# Simon.net
KiCad netlist of a schematic drawn in EAGLE
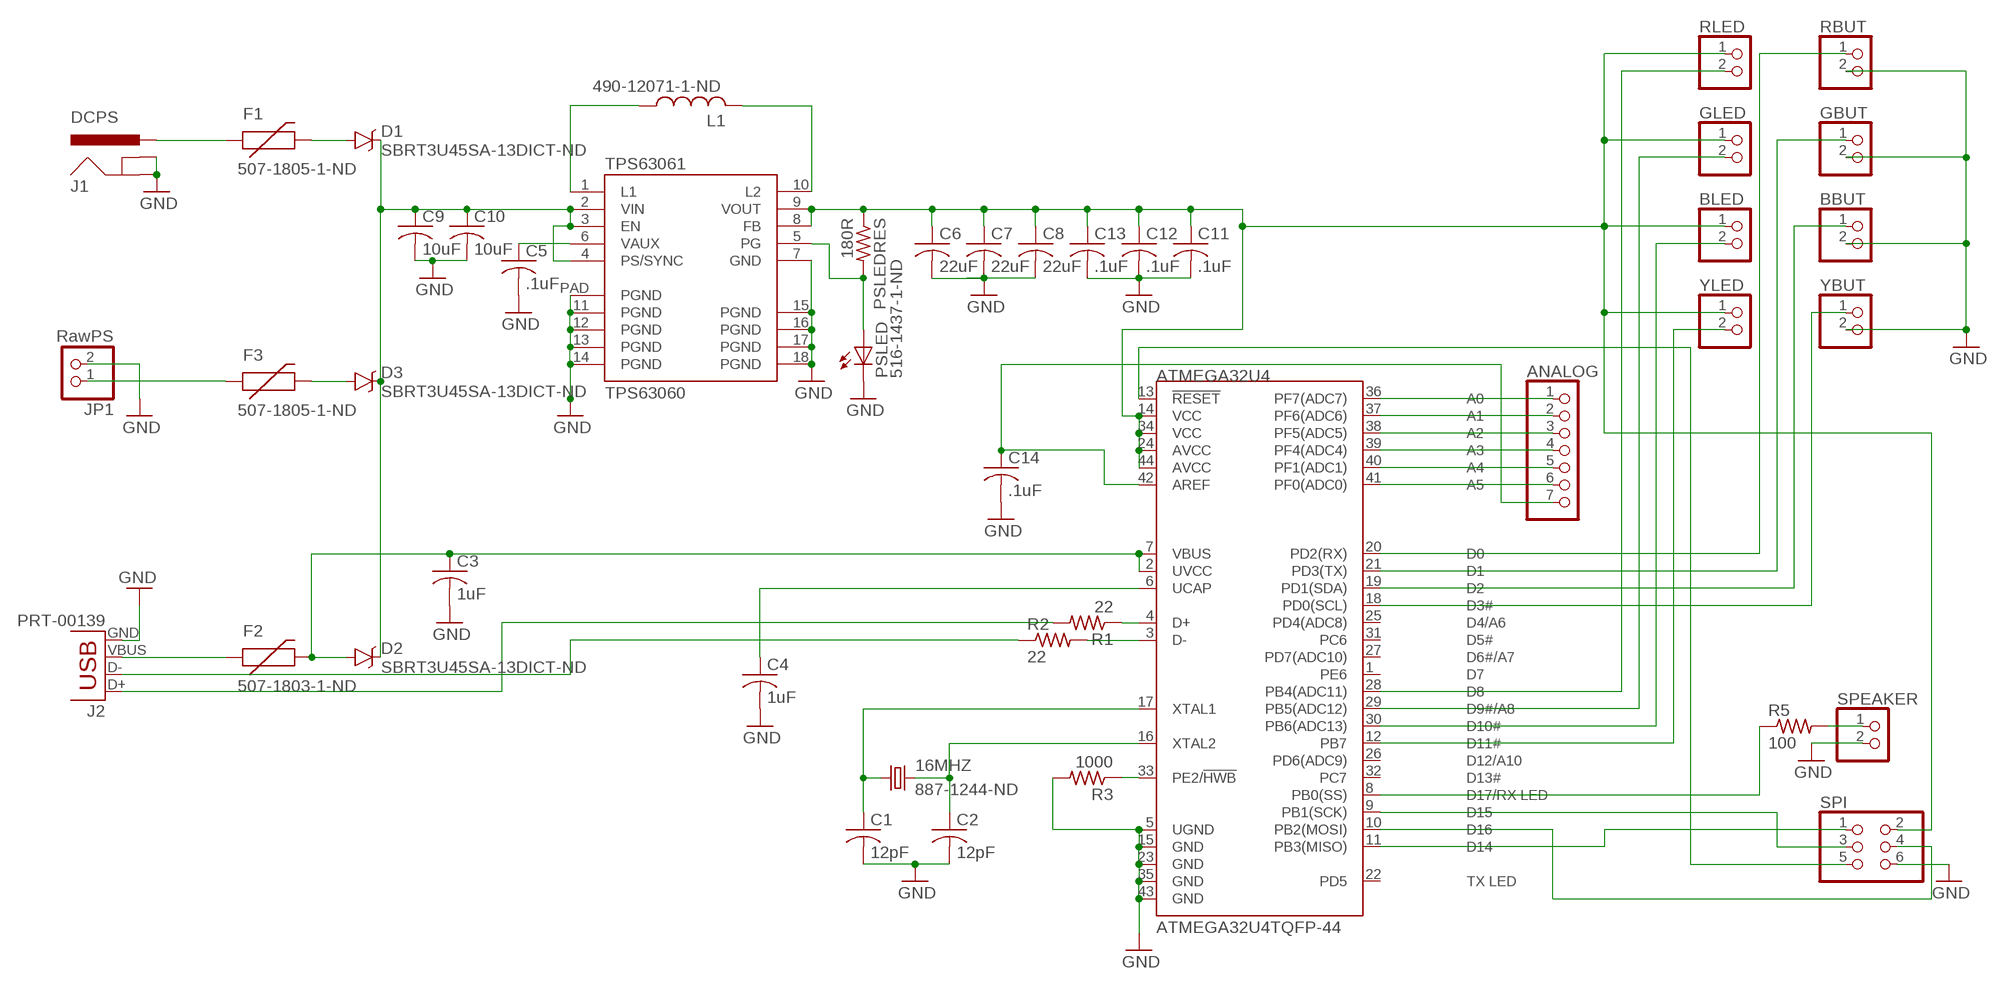
[diagram p0: schematic, sheet 1]

(export (version "E")
  (design (tool "Eeschema 10.0.6"))
  (components
    (comp (ref "16MHZ")
      (value "887-1244-ND")
      (footprint "eagle-import:HC49US")
      (libsource (lib "eagle-import") (part "CRYSTALHC49US"))
    )
    (comp (ref "ANALOG")
      (value "PINHD-1X7")
      (footprint "eagle-import:1X07")
      (libsource (lib "eagle-import") (part "PINHD-1X7"))
    )
    (comp (ref "ATMEGA32U4")
      (value "ATMEGA32U4TQFP-44")
      (footprint "eagle-import:TQFP44")
      (libsource (lib "eagle-import") (part "ATMEGA32U4TQFP-44"))
    )
    (comp (ref "BBUT")
      (value "PINHD-1X2")
      (footprint "eagle-import:1X02")
      (libsource (lib "eagle-import") (part "PINHD-1X2"))
    )
    (comp (ref "BLED")
      (value "PINHD-1X2")
      (footprint "eagle-import:1X02")
      (libsource (lib "eagle-import") (part "PINHD-1X2"))
    )
    (comp (ref "C1")
      (value "12pF")
      (footprint "eagle-import:C0805")
      (libsource (lib "eagle-import") (part "C-USC0805"))
    )
    (comp (ref "C2")
      (value "12pF")
      (footprint "eagle-import:C0805")
      (libsource (lib "eagle-import") (part "C-USC0805"))
    )
    (comp (ref "C3")
      (value "1uF")
      (footprint "eagle-import:C0805")
      (libsource (lib "eagle-import") (part "C-USC0805"))
    )
    (comp (ref "C4")
      (value "1uF")
      (footprint "eagle-import:C0805")
      (libsource (lib "eagle-import") (part "C-USC0805"))
    )
    (comp (ref "C5")
      (value ".1uF")
      (footprint "eagle-import:C0805")
      (libsource (lib "eagle-import") (part "C-USC0805"))
    )
    (comp (ref "C6")
      (value "22uF")
      (footprint "eagle-import:C0805")
      (libsource (lib "eagle-import") (part "resistor_C-USC0805"))
    )
    (comp (ref "C7")
      (value "22uF")
      (footprint "eagle-import:C0805")
      (libsource (lib "eagle-import") (part "resistor_C-USC0805"))
    )
    (comp (ref "C8")
      (value "22uF")
      (footprint "eagle-import:C0805")
      (libsource (lib "eagle-import") (part "resistor_C-USC0805"))
    )
    (comp (ref "C9")
      (value "10uF")
      (footprint "eagle-import:C0805")
      (libsource (lib "eagle-import") (part "resistor_C-USC0805"))
    )
    (comp (ref "C10")
      (value "10uF")
      (footprint "eagle-import:C0805")
      (libsource (lib "eagle-import") (part "resistor_C-USC0805"))
    )
    (comp (ref "C11")
      (value ".1uF")
      (footprint "eagle-import:C0805")
      (libsource (lib "eagle-import") (part "C-USC0805"))
    )
    (comp (ref "C12")
      (value ".1uF")
      (footprint "eagle-import:C0805")
      (libsource (lib "eagle-import") (part "C-USC0805"))
    )
    (comp (ref "C13")
      (value ".1uF")
      (footprint "eagle-import:C0805")
      (libsource (lib "eagle-import") (part "C-USC0805"))
    )
    (comp (ref "C14")
      (value ".1uF")
      (footprint "eagle-import:C0805")
      (libsource (lib "eagle-import") (part "C-USC0805"))
    )
    (comp (ref "D1")
      (value "SBRT3U45SA-13DICT-ND")
      (footprint "eagle-import:SMA-DIODE")
      (libsource (lib "eagle-import") (part "MBRA140"))
    )
    (comp (ref "D2")
      (value "SBRT3U45SA-13DICT-ND")
      (footprint "eagle-import:SMA-DIODE")
      (libsource (lib "eagle-import") (part "MBRA140"))
    )
    (comp (ref "D3")
      (value "SBRT3U45SA-13DICT-ND")
      (footprint "eagle-import:SMA-DIODE")
      (libsource (lib "eagle-import") (part "MBRA140"))
    )
    (comp (ref "F1")
      (value "507-1805-1-ND")
      (footprint "eagle-import:PTC-1206-WIDE")
      (libsource (lib "eagle-import") (part "PTCSMD-W"))
    )
    (comp (ref "F2")
      (value "507-1803-1-ND")
      (footprint "eagle-import:PTC-1206-WIDE")
      (libsource (lib "eagle-import") (part "PTCSMD-W"))
    )
    (comp (ref "F3")
      (value "507-1805-1-ND")
      (footprint "eagle-import:PTC-1206-WIDE")
      (libsource (lib "eagle-import") (part "PTCSMD-W"))
    )
    (comp (ref "GBUT")
      (value "PINHD-1X2")
      (footprint "eagle-import:1X02")
      (libsource (lib "eagle-import") (part "PINHD-1X2"))
    )
    (comp (ref "GLED")
      (value "PINHD-1X2")
      (footprint "eagle-import:1X02")
      (libsource (lib "eagle-import") (part "PINHD-1X2"))
    )
    (comp (ref "J1")
      (value "DCPS")
      (footprint "eagle-import:POWER_JACK_SMD")
      (libsource (lib "eagle-import") (part "POWER_JACKSMD"))
    )
    (comp (ref "J2")
      (value "PRT-00139")
      (footprint "eagle-import:USB-B-PTH")
      (libsource (lib "eagle-import") (part "USBPTH"))
    )
    (comp (ref "JP1")
      (value "RawPS")
      (footprint "eagle-import:1X02_90")
      (libsource (lib "eagle-import") (part "PINHD-1X2/90"))
    )
    (comp (ref "L1")
      (value "490-12071-1-ND")
      (footprint "eagle-import:L2012C")
      (libsource (lib "eagle-import") (part "L-USL2012C"))
    )
    (comp (ref "PSLED")
      (value "516-1437-1-ND")
      (footprint "eagle-import:SML0805")
      (libsource (lib "eagle-import") (part "LEDSML0805"))
    )
    (comp (ref "PSLEDRES")
      (value "180R")
      (footprint "eagle-import:R0805")
      (libsource (lib "eagle-import") (part "R-US_R0805"))
    )
    (comp (ref "R1")
      (value "22")
      (footprint "eagle-import:R0805")
      (libsource (lib "eagle-import") (part "R-US_R0805"))
    )
    (comp (ref "R2")
      (value "22")
      (footprint "eagle-import:R0805")
      (libsource (lib "eagle-import") (part "R-US_R0805"))
    )
    (comp (ref "R3")
      (value "1000")
      (footprint "eagle-import:R0805")
      (libsource (lib "eagle-import") (part "R-US_R0805"))
    )
    (comp (ref "R5")
      (value "100")
      (footprint "eagle-import:R0805")
      (libsource (lib "eagle-import") (part "R-US_R0805"))
    )
    (comp (ref "RBUT")
      (value "PINHD-1X2")
      (footprint "eagle-import:1X02")
      (libsource (lib "eagle-import") (part "PINHD-1X2"))
    )
    (comp (ref "RLED")
      (value "PINHD-1X2")
      (footprint "eagle-import:1X02")
      (libsource (lib "eagle-import") (part "PINHD-1X2"))
    )
    (comp (ref "SPEAKER")
      (value "PINHD-1X2")
      (footprint "eagle-import:1X02")
      (libsource (lib "eagle-import") (part "PINHD-1X2"))
    )
    (comp (ref "SPI")
      (value "PINHD-2X3")
      (footprint "eagle-import:2X03")
      (libsource (lib "eagle-import") (part "PINHD-2X3"))
    )
    (comp (ref "TPS63061")
      (value "TPS63060")
      (footprint "eagle-import:QFN-10_PAD-8")
      (libsource (lib "eagle-import") (part "TPS63060"))
    )
    (comp (ref "YBUT")
      (value "PINHD-1X2")
      (footprint "eagle-import:1X02")
      (libsource (lib "eagle-import") (part "PINHD-1X2"))
    )
    (comp (ref "YLED")
      (value "PINHD-1X2")
      (footprint "eagle-import:1X02")
      (libsource (lib "eagle-import") (part "PINHD-1X2"))
    )
  )
  (nets
    (net (code "1") (name "GND") (class "Default")
      (node (ref "ATMEGA32U4") (pin "15") (pinfunction "GND_15") (pintype "bidirectional"))
      (node (ref "ATMEGA32U4") (pin "23") (pinfunction "GND_23") (pintype "bidirectional"))
      (node (ref "ATMEGA32U4") (pin "35") (pinfunction "GND_35") (pintype "bidirectional"))
      (node (ref "ATMEGA32U4") (pin "43") (pinfunction "GND_43") (pintype "bidirectional"))
      (node (ref "ATMEGA32U4") (pin "5") (pinfunction "UGND_5") (pintype "bidirectional"))
      (node (ref "BBUT") (pin "2") (pinfunction "2_2") (pintype "passive"))
      (node (ref "C1") (pin "2") (pinfunction "2_2") (pintype "passive"))
      (node (ref "C10") (pin "2") (pinfunction "2_2") (pintype "passive"))
      (node (ref "C11") (pin "2") (pinfunction "2_2") (pintype "passive"))
      (node (ref "C12") (pin "2") (pinfunction "2_2") (pintype "passive"))
      (node (ref "C13") (pin "2") (pinfunction "2_2") (pintype "passive"))
      (node (ref "C14") (pin "2") (pinfunction "2_2") (pintype "passive"))
      (node (ref "C2") (pin "2") (pinfunction "2_2") (pintype "passive"))
      (node (ref "C3") (pin "2") (pinfunction "2_2") (pintype "passive"))
      (node (ref "C4") (pin "2") (pinfunction "2_2") (pintype "passive"))
      (node (ref "C5") (pin "2") (pinfunction "2_2") (pintype "passive"))
      (node (ref "C6") (pin "2") (pinfunction "2_2") (pintype "passive"))
      (node (ref "C7") (pin "2") (pinfunction "2_2") (pintype "passive"))
      (node (ref "C8") (pin "2") (pinfunction "2_2") (pintype "passive"))
      (node (ref "C9") (pin "2") (pinfunction "2_2") (pintype "passive"))
      (node (ref "GBUT") (pin "2") (pinfunction "2_2") (pintype "passive"))
      (node (ref "J1") (pin "GND") (pinfunction "GNDBREAK_GND") (pintype "bidirectional"))
      (node (ref "J1") (pin "P$4") (pinfunction "GND_P$4") (pintype "bidirectional"))
      (node (ref "J2") (pin "GND") (pinfunction "GND_GND") (pintype "bidirectional"))
      (node (ref "JP1") (pin "2") (pinfunction "2_2") (pintype "passive"))
      (node (ref "PSLED") (pin "C") (pinfunction "C_C") (pintype "passive"))
      (node (ref "R3") (pin "2") (pinfunction "2_2") (pintype "passive"))
      (node (ref "RBUT") (pin "2") (pinfunction "2_2") (pintype "passive"))
      (node (ref "SPEAKER") (pin "2") (pinfunction "2_2") (pintype "passive"))
      (node (ref "SPI") (pin "6") (pinfunction "6_6") (pintype "passive"))
      (node (ref "TPS63061") (pin "11") (pinfunction "PGND_11") (pintype "bidirectional"))
      (node (ref "TPS63061") (pin "12") (pinfunction "PGND_12") (pintype "bidirectional"))
      (node (ref "TPS63061") (pin "13") (pinfunction "PGND_13") (pintype "bidirectional"))
      (node (ref "TPS63061") (pin "14") (pinfunction "PGND_14") (pintype "bidirectional"))
      (node (ref "TPS63061") (pin "15") (pinfunction "PGND_15") (pintype "bidirectional"))
      (node (ref "TPS63061") (pin "16") (pinfunction "PGND_16") (pintype "bidirectional"))
      (node (ref "TPS63061") (pin "17") (pinfunction "PGND_17") (pintype "bidirectional"))
      (node (ref "TPS63061") (pin "18") (pinfunction "PGND_18") (pintype "bidirectional"))
      (node (ref "TPS63061") (pin "7") (pinfunction "GND_7") (pintype "bidirectional"))
      (node (ref "TPS63061") (pin "PAD") (pinfunction "PGND_PAD") (pintype "bidirectional"))
      (node (ref "YBUT") (pin "2") (pinfunction "2_2") (pintype "passive"))
    )
    (net (code "2") (name "Net-(ATMEGA32U4-AREF)") (class "Default")
      (node (ref "ANALOG") (pin "7") (pinfunction "7_7") (pintype "passive"))
      (node (ref "ATMEGA32U4") (pin "42") (pinfunction "AREF_42") (pintype "bidirectional"))
      (node (ref "C14") (pin "1") (pinfunction "1_1") (pintype "passive"))
    )
    (net (code "3") (name "Net-(ATMEGA32U4-D+)") (class "Default")
      (node (ref "ATMEGA32U4") (pin "4") (pinfunction "D+_4") (pintype "bidirectional"))
      (node (ref "R1") (pin "1") (pinfunction "1_1") (pintype "passive"))
    )
    (net (code "4") (name "Net-(ATMEGA32U4-D-)") (class "Default")
      (node (ref "ATMEGA32U4") (pin "3") (pinfunction "D-_3") (pintype "bidirectional"))
      (node (ref "R2") (pin "2") (pinfunction "2_2") (pintype "passive"))
    )
    (net (code "5") (name "Net-(ATMEGA32U4-PB0(SS))") (class "Default")
      (node (ref "ATMEGA32U4") (pin "8") (pinfunction "PB0(SS)_8") (pintype "bidirectional"))
      (node (ref "R5") (pin "1") (pinfunction "1_1") (pintype "passive"))
    )
    (net (code "6") (name "Net-(ATMEGA32U4-PB1(SCK))") (class "Default")
      (node (ref "ATMEGA32U4") (pin "9") (pinfunction "PB1(SCK)_9") (pintype "bidirectional"))
      (node (ref "SPI") (pin "3") (pinfunction "3_3") (pintype "passive"))
    )
    (net (code "7") (name "Net-(ATMEGA32U4-PB2(MOSI))") (class "Default")
      (node (ref "ATMEGA32U4") (pin "10") (pinfunction "PB2(MOSI)_10") (pintype "bidirectional"))
      (node (ref "SPI") (pin "4") (pinfunction "4_4") (pintype "passive"))
    )
    (net (code "8") (name "Net-(ATMEGA32U4-PB3(MISO))") (class "Default")
      (node (ref "ATMEGA32U4") (pin "11") (pinfunction "PB3(MISO)_11") (pintype "bidirectional"))
      (node (ref "SPI") (pin "1") (pinfunction "1_1") (pintype "passive"))
    )
    (net (code "9") (name "Net-(ATMEGA32U4-PB4(ADC11))") (class "Default")
      (node (ref "ATMEGA32U4") (pin "28") (pinfunction "PB4(ADC11)_28") (pintype "bidirectional"))
      (node (ref "RLED") (pin "2") (pinfunction "2_2") (pintype "passive"))
    )
    (net (code "10") (name "Net-(ATMEGA32U4-PB5(ADC12))") (class "Default")
      (node (ref "ATMEGA32U4") (pin "29") (pinfunction "PB5(ADC12)_29") (pintype "bidirectional"))
      (node (ref "GLED") (pin "2") (pinfunction "2_2") (pintype "passive"))
    )
    (net (code "11") (name "Net-(ATMEGA32U4-PB6(ADC13))") (class "Default")
      (node (ref "ATMEGA32U4") (pin "30") (pinfunction "PB6(ADC13)_30") (pintype "bidirectional"))
      (node (ref "BLED") (pin "2") (pinfunction "2_2") (pintype "passive"))
    )
    (net (code "12") (name "Net-(ATMEGA32U4-PB7)") (class "Default")
      (node (ref "ATMEGA32U4") (pin "12") (pinfunction "PB7_12") (pintype "bidirectional"))
      (node (ref "YLED") (pin "2") (pinfunction "2_2") (pintype "passive"))
    )
    (net (code "13") (name "Net-(ATMEGA32U4-PD0(SCL))") (class "Default")
      (node (ref "ATMEGA32U4") (pin "18") (pinfunction "PD0(SCL)_18") (pintype "bidirectional"))
      (node (ref "YBUT") (pin "1") (pinfunction "1_1") (pintype "passive"))
    )
    (net (code "14") (name "Net-(ATMEGA32U4-PD1(SDA))") (class "Default")
      (node (ref "ATMEGA32U4") (pin "19") (pinfunction "PD1(SDA)_19") (pintype "bidirectional"))
      (node (ref "BBUT") (pin "1") (pinfunction "1_1") (pintype "passive"))
    )
    (net (code "15") (name "Net-(ATMEGA32U4-PD2(RX))") (class "Default")
      (node (ref "ATMEGA32U4") (pin "20") (pinfunction "PD2(RX)_20") (pintype "bidirectional"))
      (node (ref "RBUT") (pin "1") (pinfunction "1_1") (pintype "passive"))
    )
    (net (code "16") (name "Net-(ATMEGA32U4-PD3(TX))") (class "Default")
      (node (ref "ATMEGA32U4") (pin "21") (pinfunction "PD3(TX)_21") (pintype "bidirectional"))
      (node (ref "GBUT") (pin "1") (pinfunction "1_1") (pintype "passive"))
    )
    (net (code "17") (name "Net-(ATMEGA32U4-PE2{slash}~{HWB})") (class "Default")
      (node (ref "ATMEGA32U4") (pin "33") (pinfunction "PE2/~{HWB}_33") (pintype "bidirectional"))
      (node (ref "R3") (pin "1") (pinfunction "1_1") (pintype "passive"))
    )
    (net (code "18") (name "Net-(ATMEGA32U4-PF0(ADC0))") (class "Default")
      (node (ref "ANALOG") (pin "6") (pinfunction "6_6") (pintype "passive"))
      (node (ref "ATMEGA32U4") (pin "41") (pinfunction "PF0(ADC0)_41") (pintype "bidirectional"))
    )
    (net (code "19") (name "Net-(ATMEGA32U4-PF1(ADC1))") (class "Default")
      (node (ref "ANALOG") (pin "5") (pinfunction "5_5") (pintype "passive"))
      (node (ref "ATMEGA32U4") (pin "40") (pinfunction "PF1(ADC1)_40") (pintype "bidirectional"))
    )
    (net (code "20") (name "Net-(ATMEGA32U4-PF4(ADC4))") (class "Default")
      (node (ref "ANALOG") (pin "4") (pinfunction "4_4") (pintype "passive"))
      (node (ref "ATMEGA32U4") (pin "39") (pinfunction "PF4(ADC4)_39") (pintype "bidirectional"))
    )
    (net (code "21") (name "Net-(ATMEGA32U4-PF5(ADC5))") (class "Default")
      (node (ref "ANALOG") (pin "3") (pinfunction "3_3") (pintype "passive"))
      (node (ref "ATMEGA32U4") (pin "38") (pinfunction "PF5(ADC5)_38") (pintype "bidirectional"))
    )
    (net (code "22") (name "Net-(ATMEGA32U4-PF6(ADC6))") (class "Default")
      (node (ref "ANALOG") (pin "2") (pinfunction "2_2") (pintype "passive"))
      (node (ref "ATMEGA32U4") (pin "37") (pinfunction "PF6(ADC6)_37") (pintype "bidirectional"))
    )
    (net (code "23") (name "Net-(ATMEGA32U4-PF7(ADC7))") (class "Default")
      (node (ref "ANALOG") (pin "1") (pinfunction "1_1") (pintype "passive"))
      (node (ref "ATMEGA32U4") (pin "36") (pinfunction "PF7(ADC7)_36") (pintype "bidirectional"))
    )
    (net (code "24") (name "Net-(ATMEGA32U4-UCAP)") (class "Default")
      (node (ref "ATMEGA32U4") (pin "6") (pinfunction "UCAP_6") (pintype "bidirectional"))
      (node (ref "C4") (pin "1") (pinfunction "1_1") (pintype "passive"))
    )
    (net (code "25") (name "Net-(ATMEGA32U4-UVCC)") (class "Default")
      (node (ref "ATMEGA32U4") (pin "2") (pinfunction "UVCC_2") (pintype "bidirectional"))
      (node (ref "ATMEGA32U4") (pin "7") (pinfunction "VBUS_7") (pintype "bidirectional"))
      (node (ref "C3") (pin "1") (pinfunction "1_1") (pintype "passive"))
      (node (ref "D2") (pin "A") (pinfunction "A_A") (pintype "passive"))
      (node (ref "F2") (pin "2") (pinfunction "2_2") (pintype "bidirectional"))
    )
    (net (code "26") (name "Net-(ATMEGA32U4-XTAL1)") (class "Default")
      (node (ref "16MHZ") (pin "1") (pinfunction "1_1") (pintype "passive"))
      (node (ref "ATMEGA32U4") (pin "17") (pinfunction "XTAL1_17") (pintype "bidirectional"))
      (node (ref "C1") (pin "1") (pinfunction "1_1") (pintype "passive"))
    )
    (net (code "27") (name "Net-(ATMEGA32U4-XTAL2)") (class "Default")
      (node (ref "16MHZ") (pin "2") (pinfunction "2_2") (pintype "passive"))
      (node (ref "ATMEGA32U4") (pin "16") (pinfunction "XTAL2_16") (pintype "bidirectional"))
      (node (ref "C2") (pin "1") (pinfunction "1_1") (pintype "passive"))
    )
    (net (code "28") (name "Net-(ATMEGA32U4-~{RESET})") (class "Default")
      (node (ref "ATMEGA32U4") (pin "13") (pinfunction "~{RESET}_13") (pintype "bidirectional"))
      (node (ref "SPI") (pin "5") (pinfunction "5_5") (pintype "passive"))
    )
    (net (code "29") (name "Net-(D1-PadA)") (class "Default")
      (node (ref "D1") (pin "A") (pinfunction "A_A") (pintype "passive"))
      (node (ref "F1") (pin "2") (pinfunction "2_2") (pintype "bidirectional"))
    )
    (net (code "30") (name "Net-(D3-PadA)") (class "Default")
      (node (ref "D3") (pin "A") (pinfunction "A_A") (pintype "passive"))
      (node (ref "F3") (pin "2") (pinfunction "2_2") (pintype "bidirectional"))
    )
    (net (code "31") (name "Net-(F2-Pad1)") (class "Default")
      (node (ref "F2") (pin "1") (pinfunction "1_1") (pintype "bidirectional"))
      (node (ref "J2") (pin "VBUS") (pinfunction "VBUS_VBUS") (pintype "bidirectional"))
    )
    (net (code "32") (name "Net-(F3-Pad1)") (class "Default")
      (node (ref "F3") (pin "1") (pinfunction "1_1") (pintype "bidirectional"))
      (node (ref "JP1") (pin "1") (pinfunction "1_1") (pintype "passive"))
    )
    (net (code "33") (name "Net-(J1-PWR)") (class "Default")
      (node (ref "F1") (pin "1") (pinfunction "1_1") (pintype "bidirectional"))
      (node (ref "J1") (pin "VIN0") (pinfunction "PWR_VIN0") (pintype "bidirectional"))
    )
    (net (code "34") (name "Net-(J2-PadD+)") (class "Default")
      (node (ref "J2") (pin "D+") (pinfunction "D+_D+") (pintype "bidirectional"))
      (node (ref "R1") (pin "2") (pinfunction "2_2") (pintype "passive"))
    )
    (net (code "35") (name "Net-(J2-PadD-)") (class "Default")
      (node (ref "J2") (pin "D-") (pinfunction "D-_D-") (pintype "bidirectional"))
      (node (ref "R2") (pin "1") (pinfunction "1_1") (pintype "passive"))
    )
    (net (code "36") (name "Net-(R5-Pad2)") (class "Default")
      (node (ref "R5") (pin "2") (pinfunction "2_2") (pintype "passive"))
      (node (ref "SPEAKER") (pin "1") (pinfunction "1_1") (pintype "passive"))
    )
    (net (code "37") (name "Net-(TPS63061-EN)") (class "Default")
      (node (ref "C10") (pin "1") (pinfunction "1_1") (pintype "passive"))
      (node (ref "C9") (pin "1") (pinfunction "1_1") (pintype "passive"))
      (node (ref "D1") (pin "C") (pinfunction "C_C") (pintype "passive"))
      (node (ref "D2") (pin "C") (pinfunction "C_C") (pintype "passive"))
      (node (ref "D3") (pin "C") (pinfunction "C_C") (pintype "passive"))
      (node (ref "TPS63061") (pin "2") (pinfunction "VIN_2") (pintype "bidirectional"))
      (node (ref "TPS63061") (pin "3") (pinfunction "EN_3") (pintype "bidirectional"))
      (node (ref "TPS63061") (pin "4") (pinfunction "PS/SYNC_4") (pintype "bidirectional"))
    )
    (net (code "38") (name "Net-(TPS63061-FB)") (class "Default")
      (node (ref "ATMEGA32U4") (pin "14") (pinfunction "VCC_14") (pintype "bidirectional"))
      (node (ref "ATMEGA32U4") (pin "24") (pinfunction "AVCC_24") (pintype "bidirectional"))
      (node (ref "ATMEGA32U4") (pin "34") (pinfunction "VCC_34") (pintype "bidirectional"))
      (node (ref "ATMEGA32U4") (pin "44") (pinfunction "AVCC_44") (pintype "bidirectional"))
      (node (ref "BLED") (pin "1") (pinfunction "1_1") (pintype "passive"))
      (node (ref "C11") (pin "1") (pinfunction "1_1") (pintype "passive"))
      (node (ref "C12") (pin "1") (pinfunction "1_1") (pintype "passive"))
      (node (ref "C13") (pin "1") (pinfunction "1_1") (pintype "passive"))
      (node (ref "C6") (pin "1") (pinfunction "1_1") (pintype "passive"))
      (node (ref "C7") (pin "1") (pinfunction "1_1") (pintype "passive"))
      (node (ref "C8") (pin "1") (pinfunction "1_1") (pintype "passive"))
      (node (ref "GLED") (pin "1") (pinfunction "1_1") (pintype "passive"))
      (node (ref "PSLEDRES") (pin "1") (pinfunction "1_1") (pintype "passive"))
      (node (ref "RLED") (pin "1") (pinfunction "1_1") (pintype "passive"))
      (node (ref "SPI") (pin "2") (pinfunction "2_2") (pintype "passive"))
      (node (ref "TPS63061") (pin "8") (pinfunction "FB_8") (pintype "bidirectional"))
      (node (ref "TPS63061") (pin "9") (pinfunction "VOUT_9") (pintype "bidirectional"))
      (node (ref "YLED") (pin "1") (pinfunction "1_1") (pintype "passive"))
    )
    (net (code "39") (name "Net-(TPS63061-L1)") (class "Default")
      (node (ref "L1") (pin "1") (pinfunction "1_1") (pintype "passive"))
      (node (ref "TPS63061") (pin "1") (pinfunction "L1_1") (pintype "bidirectional"))
    )
    (net (code "40") (name "Net-(TPS63061-L2)") (class "Default")
      (node (ref "L1") (pin "2") (pinfunction "2_2") (pintype "passive"))
      (node (ref "TPS63061") (pin "10") (pinfunction "L2_10") (pintype "bidirectional"))
    )
    (net (code "41") (name "Net-(TPS63061-PG)") (class "Default")
      (node (ref "PSLED") (pin "A") (pinfunction "A_A") (pintype "passive"))
      (node (ref "PSLEDRES") (pin "2") (pinfunction "2_2") (pintype "passive"))
      (node (ref "TPS63061") (pin "5") (pinfunction "PG_5") (pintype "bidirectional"))
    )
    (net (code "42") (name "Net-(TPS63061-VAUX)") (class "Default")
      (node (ref "C5") (pin "1") (pinfunction "1_1") (pintype "passive"))
      (node (ref "TPS63061") (pin "6") (pinfunction "VAUX_6") (pintype "bidirectional"))
    )
    (net (code "43") (name "unconnected-(ATMEGA32U4-PC6-Pad31)") (class "Default")
      (node (ref "ATMEGA32U4") (pin "31") (pinfunction "PC6_31") (pintype "bidirectional"))
    )
    (net (code "44") (name "unconnected-(ATMEGA32U4-PC7-Pad32)") (class "Default")
      (node (ref "ATMEGA32U4") (pin "32") (pinfunction "PC7_32") (pintype "bidirectional"))
    )
    (net (code "45") (name "unconnected-(ATMEGA32U4-PD4(ADC8)-Pad25)") (class "Default")
      (node (ref "ATMEGA32U4") (pin "25") (pinfunction "PD4(ADC8)_25") (pintype "bidirectional"))
    )
    (net (code "46") (name "unconnected-(ATMEGA32U4-PD5-Pad22)") (class "Default")
      (node (ref "ATMEGA32U4") (pin "22") (pinfunction "PD5_22") (pintype "bidirectional"))
    )
    (net (code "47") (name "unconnected-(ATMEGA32U4-PD6(ADC9)-Pad26)") (class "Default")
      (node (ref "ATMEGA32U4") (pin "26") (pinfunction "PD6(ADC9)_26") (pintype "bidirectional"))
    )
    (net (code "48") (name "unconnected-(ATMEGA32U4-PD7(ADC10)-Pad27)") (class "Default")
      (node (ref "ATMEGA32U4") (pin "27") (pinfunction "PD7(ADC10)_27") (pintype "bidirectional"))
    )
    (net (code "49") (name "unconnected-(ATMEGA32U4-PE6-Pad1)") (class "Default")
      (node (ref "ATMEGA32U4") (pin "1") (pinfunction "PE6_1") (pintype "bidirectional"))
    )
  )
)
